# 06-5V_To_3V3.net
KiCad netlist of a schematic drawn in Altium Designer
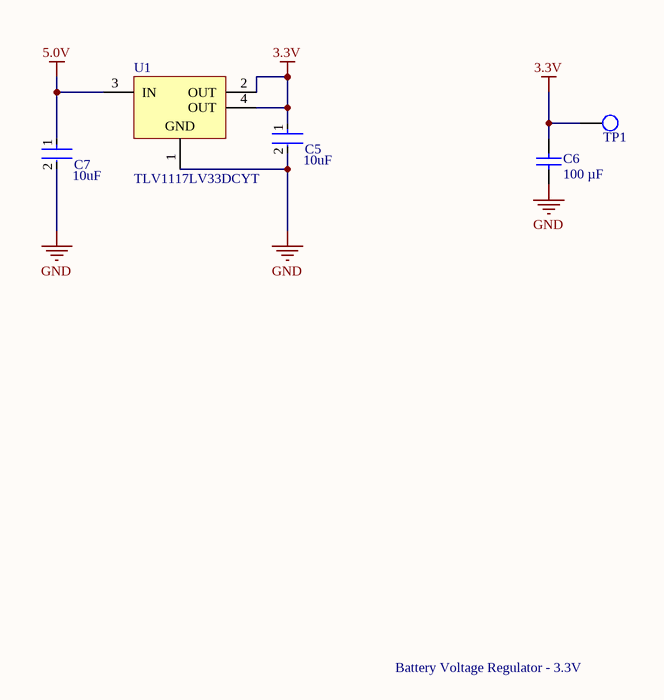
[diagram p0: 06-5V_To_3V3.SchDoc]

(export (version "E")
  (design (tool "Eeschema 10.0.6"))
  (components
    (comp (ref "C5")
      (value "CL21A106KQCLNNC")
      (footprint "FP-CL21-IPC_B")
      (description "CL21 Series 0805 10uF 6.3V ±10% Tolerance X5R Multilayer Ceramic Chip Capacitor")
      (fields (field (name "CAPACITANCE") "10uF") (field (name "TOLERANCE") "10%"))
      (libsource (lib "Altium Content Vault") (part "b4654b650e69147ec39a6b967a45e02"))
    )
    (comp (ref "C6")
      (value "EEEHA1A101WP")
      (footprint "CAP_EEEHA1A101WP")
      (description "100ÂµF 10V Aluminum Electrolytic Capacitors Radial, Can - SMD 1000 Hrs @ 105Â°C")
      (fields
        (field (name "MF") "Panasonic")
        (field (name "MP") "EEE-HA1A101WP")
        (field (name "CAPACITANCE") "100 µF")
      )
      (libsource (lib "team6") (part "EEEHA1A101WP"))
    )
    (comp (ref "C7")
      (value "CL21A106KQCLNNC")
      (footprint "FP-CL21-IPC_B")
      (description "CL21 Series 0805 10uF 6.3V ±10% Tolerance X5R Multilayer Ceramic Chip Capacitor")
      (fields (field (name "CAPACITANCE") "10uF") (field (name "TOLERANCE") "10%"))
      (libsource (lib "Altium Content Vault") (part "b4654b650e69147ec39a6b967a45e02"))
    )
    (comp (ref "TP1")
      (value "TP_1206")
      (footprint "TP-SMC-1206")
      (description "Test Point SMD 1206")
      (fields
        (field (name "MANUFACTURER") "TE Connectivity (Tyco Electronics)")
        (field (name "MANUFACTURER PART NUMBER") "1625854-1")
      )
      (libsource (lib "ECE453-F22-Power") (part "TP_1206"))
    )
    (comp (ref "U1")
      (value "TLV1117LV33DCYT")
      (footprint "DCY0004A_M")
      (fields (field (name "MANUFACTURER") "Texas Instruments"))
      (libsource (lib "Altium Content Vault") (part "TI-TLV1117LV33DCY4"))
    )
  )
  (nets
    (net (code "1") (name "3.3V") (class "Default")
      (node (ref "C5") (pin "1") (pinfunction "1_1") (pintype "passive"))
      (node (ref "C6") (pin "2") (pinfunction "2_2") (pintype "passive"))
      (node (ref "TP1") (pin "1") (pintype "passive"))
      (node (ref "U1") (pin "2") (pinfunction "OUT_2") (pintype "power_in"))
      (node (ref "U1") (pin "4") (pinfunction "OUT_4") (pintype "power_in"))
    )
    (net (code "2") (name "5.0V") (class "Default")
      (node (ref "C7") (pin "1") (pinfunction "1_1") (pintype "passive"))
      (node (ref "U1") (pin "3") (pinfunction "IN_3") (pintype "power_in"))
    )
    (net (code "3") (name "GND") (class "Default")
      (node (ref "C5") (pin "2") (pinfunction "2_2") (pintype "passive"))
      (node (ref "C6") (pin "1") (pinfunction "1_1") (pintype "passive"))
      (node (ref "C7") (pin "2") (pinfunction "2_2") (pintype "passive"))
      (node (ref "U1") (pin "1") (pinfunction "GND_1") (pintype "power_in"))
    )
  )
)
